# Volt4-leds.net
KiCad netlist of a schematic drawn in EAGLE
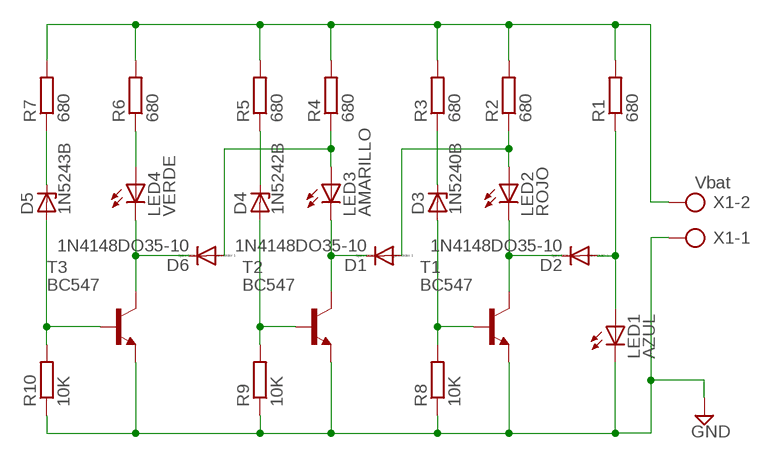
[diagram p0: schematic, sheet 1]

(export (version "E")
  (design (tool "Eeschema 10.0.6"))
  (components
    (comp (ref "D1")
      (value "1N4148DO35-10")
      (footprint "eagle-import:DO35-10")
      (libsource (lib "eagle-import") (part "1N4148DO35-10"))
    )
    (comp (ref "D2")
      (value "1N4148DO35-10")
      (footprint "eagle-import:DO35-10")
      (libsource (lib "eagle-import") (part "1N4148DO35-10"))
    )
    (comp (ref "D3")
      (value "1N5240B")
      (footprint "eagle-import:DO35Z10")
      (libsource (lib "eagle-import") (part "ZENER-DIODEDO35Z10"))
    )
    (comp (ref "D4")
      (value "1N5242B")
      (footprint "eagle-import:DO35Z10")
      (libsource (lib "eagle-import") (part "ZENER-DIODEDO35Z10"))
    )
    (comp (ref "D5")
      (value "1N5243B")
      (footprint "eagle-import:DO35Z10")
      (libsource (lib "eagle-import") (part "ZENER-DIODEDO35Z10"))
    )
    (comp (ref "D6")
      (value "1N4148DO35-10")
      (footprint "eagle-import:DO35-10")
      (libsource (lib "eagle-import") (part "1N4148DO35-10"))
    )
    (comp (ref "LED1")
      (value "AZUL")
      (footprint "eagle-import:LED3MM")
      (libsource (lib "eagle-import") (part "LED3MM"))
    )
    (comp (ref "LED2")
      (value "ROJO")
      (footprint "eagle-import:LED3MM")
      (libsource (lib "eagle-import") (part "LED3MM"))
    )
    (comp (ref "LED3")
      (value "AMARILLO")
      (footprint "eagle-import:LED3MM")
      (libsource (lib "eagle-import") (part "LED3MM"))
    )
    (comp (ref "LED4")
      (value "VERDE")
      (footprint "eagle-import:LED3MM")
      (libsource (lib "eagle-import") (part "LED3MM"))
    )
    (comp (ref "R1")
      (value "680")
      (footprint "eagle-import:0207_10")
      (libsource (lib "eagle-import") (part "R-EU_0207/10"))
    )
    (comp (ref "R2")
      (value "680")
      (footprint "eagle-import:0207_10")
      (libsource (lib "eagle-import") (part "R-EU_0207/10"))
    )
    (comp (ref "R3")
      (value "680")
      (footprint "eagle-import:0207_10")
      (libsource (lib "eagle-import") (part "R-EU_0207/10"))
    )
    (comp (ref "R4")
      (value "680")
      (footprint "eagle-import:0207_10")
      (libsource (lib "eagle-import") (part "R-EU_0207/10"))
    )
    (comp (ref "R5")
      (value "680")
      (footprint "eagle-import:0207_10")
      (libsource (lib "eagle-import") (part "R-EU_0207/10"))
    )
    (comp (ref "R6")
      (value "680")
      (footprint "eagle-import:0207_10")
      (libsource (lib "eagle-import") (part "R-EU_0207/10"))
    )
    (comp (ref "R7")
      (value "680")
      (footprint "eagle-import:0207_10")
      (libsource (lib "eagle-import") (part "R-EU_0207/10"))
    )
    (comp (ref "R8")
      (value "10K")
      (footprint "eagle-import:0207_10")
      (libsource (lib "eagle-import") (part "R-EU_0207/10"))
    )
    (comp (ref "R9")
      (value "10K")
      (footprint "eagle-import:0207_10")
      (libsource (lib "eagle-import") (part "R-EU_0207/10"))
    )
    (comp (ref "R10")
      (value "10K")
      (footprint "eagle-import:0207_10")
      (libsource (lib "eagle-import") (part "R-EU_0207/10"))
    )
    (comp (ref "T1")
      (value "BC547")
      (footprint "eagle-import:TO92")
      (libsource (lib "eagle-import") (part "BC547"))
    )
    (comp (ref "T2")
      (value "BC547")
      (footprint "eagle-import:TO92")
      (libsource (lib "eagle-import") (part "BC547"))
    )
    (comp (ref "T3")
      (value "BC547")
      (footprint "eagle-import:TO92")
      (libsource (lib "eagle-import") (part "BC547"))
    )
    (comp (ref "X1")
      (value "Vbat")
      (footprint "eagle-import:AK500_2")
      (libsource (lib "eagle-import") (part "AK500/2"))
    )
  )
  (nets
    (net (code "1") (name "GND") (class "Default")
      (node (ref "LED1") (pin "K") (pinfunction "C_K") (pintype "passive"))
      (node (ref "R10") (pin "1") (pinfunction "1_1") (pintype "passive"))
      (node (ref "R8") (pin "1") (pinfunction "1_1") (pintype "passive"))
      (node (ref "R9") (pin "1") (pinfunction "1_1") (pintype "passive"))
      (node (ref "T1") (pin "1") (pinfunction "E_1") (pintype "passive"))
      (node (ref "T2") (pin "1") (pinfunction "E_1") (pintype "passive"))
      (node (ref "T3") (pin "1") (pinfunction "E_1") (pintype "passive"))
      (node (ref "X1") (pin "1") (pinfunction "KL_1") (pintype "passive"))
    )
    (net (code "2") (name "Net-(D1-PadA)") (class "Default")
      (node (ref "D1") (pin "A") (pinfunction "A_A") (pintype "passive"))
      (node (ref "LED2") (pin "A") (pinfunction "A_A") (pintype "passive"))
      (node (ref "R2") (pin "1") (pinfunction "1_1") (pintype "passive"))
    )
    (net (code "3") (name "Net-(D2-PadA)") (class "Default")
      (node (ref "D2") (pin "A") (pinfunction "A_A") (pintype "passive"))
      (node (ref "LED1") (pin "A") (pinfunction "A_A") (pintype "passive"))
      (node (ref "R1") (pin "1") (pinfunction "1_1") (pintype "passive"))
    )
    (net (code "4") (name "Net-(D3-PadC)") (class "Default")
      (node (ref "D3") (pin "C") (pinfunction "C_C") (pintype "passive"))
      (node (ref "R3") (pin "1") (pinfunction "1_1") (pintype "passive"))
    )
    (net (code "5") (name "Net-(D4-PadC)") (class "Default")
      (node (ref "D4") (pin "C") (pinfunction "C_C") (pintype "passive"))
      (node (ref "R5") (pin "1") (pinfunction "1_1") (pintype "passive"))
    )
    (net (code "6") (name "Net-(D5-PadC)") (class "Default")
      (node (ref "D5") (pin "C") (pinfunction "C_C") (pintype "passive"))
      (node (ref "R7") (pin "1") (pinfunction "1_1") (pintype "passive"))
    )
    (net (code "7") (name "Net-(D6-PadA)") (class "Default")
      (node (ref "D6") (pin "A") (pinfunction "A_A") (pintype "passive"))
      (node (ref "LED3") (pin "A") (pinfunction "A_A") (pintype "passive"))
      (node (ref "R4") (pin "1") (pinfunction "1_1") (pintype "passive"))
    )
    (net (code "8") (name "Net-(LED2-C)") (class "Default")
      (node (ref "D2") (pin "C") (pinfunction "C_C") (pintype "passive"))
      (node (ref "LED2") (pin "K") (pinfunction "C_K") (pintype "passive"))
      (node (ref "T1") (pin "3") (pinfunction "C_3") (pintype "passive"))
    )
    (net (code "9") (name "Net-(LED3-C)") (class "Default")
      (node (ref "D1") (pin "C") (pinfunction "C_C") (pintype "passive"))
      (node (ref "LED3") (pin "K") (pinfunction "C_K") (pintype "passive"))
      (node (ref "T2") (pin "3") (pinfunction "C_3") (pintype "passive"))
    )
    (net (code "10") (name "Net-(LED4-C)") (class "Default")
      (node (ref "D6") (pin "C") (pinfunction "C_C") (pintype "passive"))
      (node (ref "LED4") (pin "K") (pinfunction "C_K") (pintype "passive"))
      (node (ref "T3") (pin "3") (pinfunction "C_3") (pintype "passive"))
    )
    (net (code "11") (name "Net-(LED4-PadA)") (class "Default")
      (node (ref "LED4") (pin "A") (pinfunction "A_A") (pintype "passive"))
      (node (ref "R6") (pin "1") (pinfunction "1_1") (pintype "passive"))
    )
    (net (code "12") (name "Net-(T1-B)") (class "Default")
      (node (ref "D3") (pin "A") (pinfunction "A_A") (pintype "passive"))
      (node (ref "R8") (pin "2") (pinfunction "2_2") (pintype "passive"))
      (node (ref "T1") (pin "2") (pinfunction "B_2") (pintype "passive"))
    )
    (net (code "13") (name "Net-(T2-B)") (class "Default")
      (node (ref "D4") (pin "A") (pinfunction "A_A") (pintype "passive"))
      (node (ref "R9") (pin "2") (pinfunction "2_2") (pintype "passive"))
      (node (ref "T2") (pin "2") (pinfunction "B_2") (pintype "passive"))
    )
    (net (code "14") (name "Net-(T3-B)") (class "Default")
      (node (ref "D5") (pin "A") (pinfunction "A_A") (pintype "passive"))
      (node (ref "R10") (pin "2") (pinfunction "2_2") (pintype "passive"))
      (node (ref "T3") (pin "2") (pinfunction "B_2") (pintype "passive"))
    )
    (net (code "15") (name "Net-(X1B-KL)") (class "Default")
      (node (ref "R1") (pin "2") (pinfunction "2_2") (pintype "passive"))
      (node (ref "R2") (pin "2") (pinfunction "2_2") (pintype "passive"))
      (node (ref "R3") (pin "2") (pinfunction "2_2") (pintype "passive"))
      (node (ref "R4") (pin "2") (pinfunction "2_2") (pintype "passive"))
      (node (ref "R5") (pin "2") (pinfunction "2_2") (pintype "passive"))
      (node (ref "R6") (pin "2") (pinfunction "2_2") (pintype "passive"))
      (node (ref "R7") (pin "2") (pinfunction "2_2") (pintype "passive"))
      (node (ref "X1") (pin "2") (pinfunction "KL_2") (pintype "passive"))
    )
  )
)
